# I-GAUGE_arduino_pro_mini_Instalasi_2.net
KiCad netlist of a schematic drawn in EAGLE
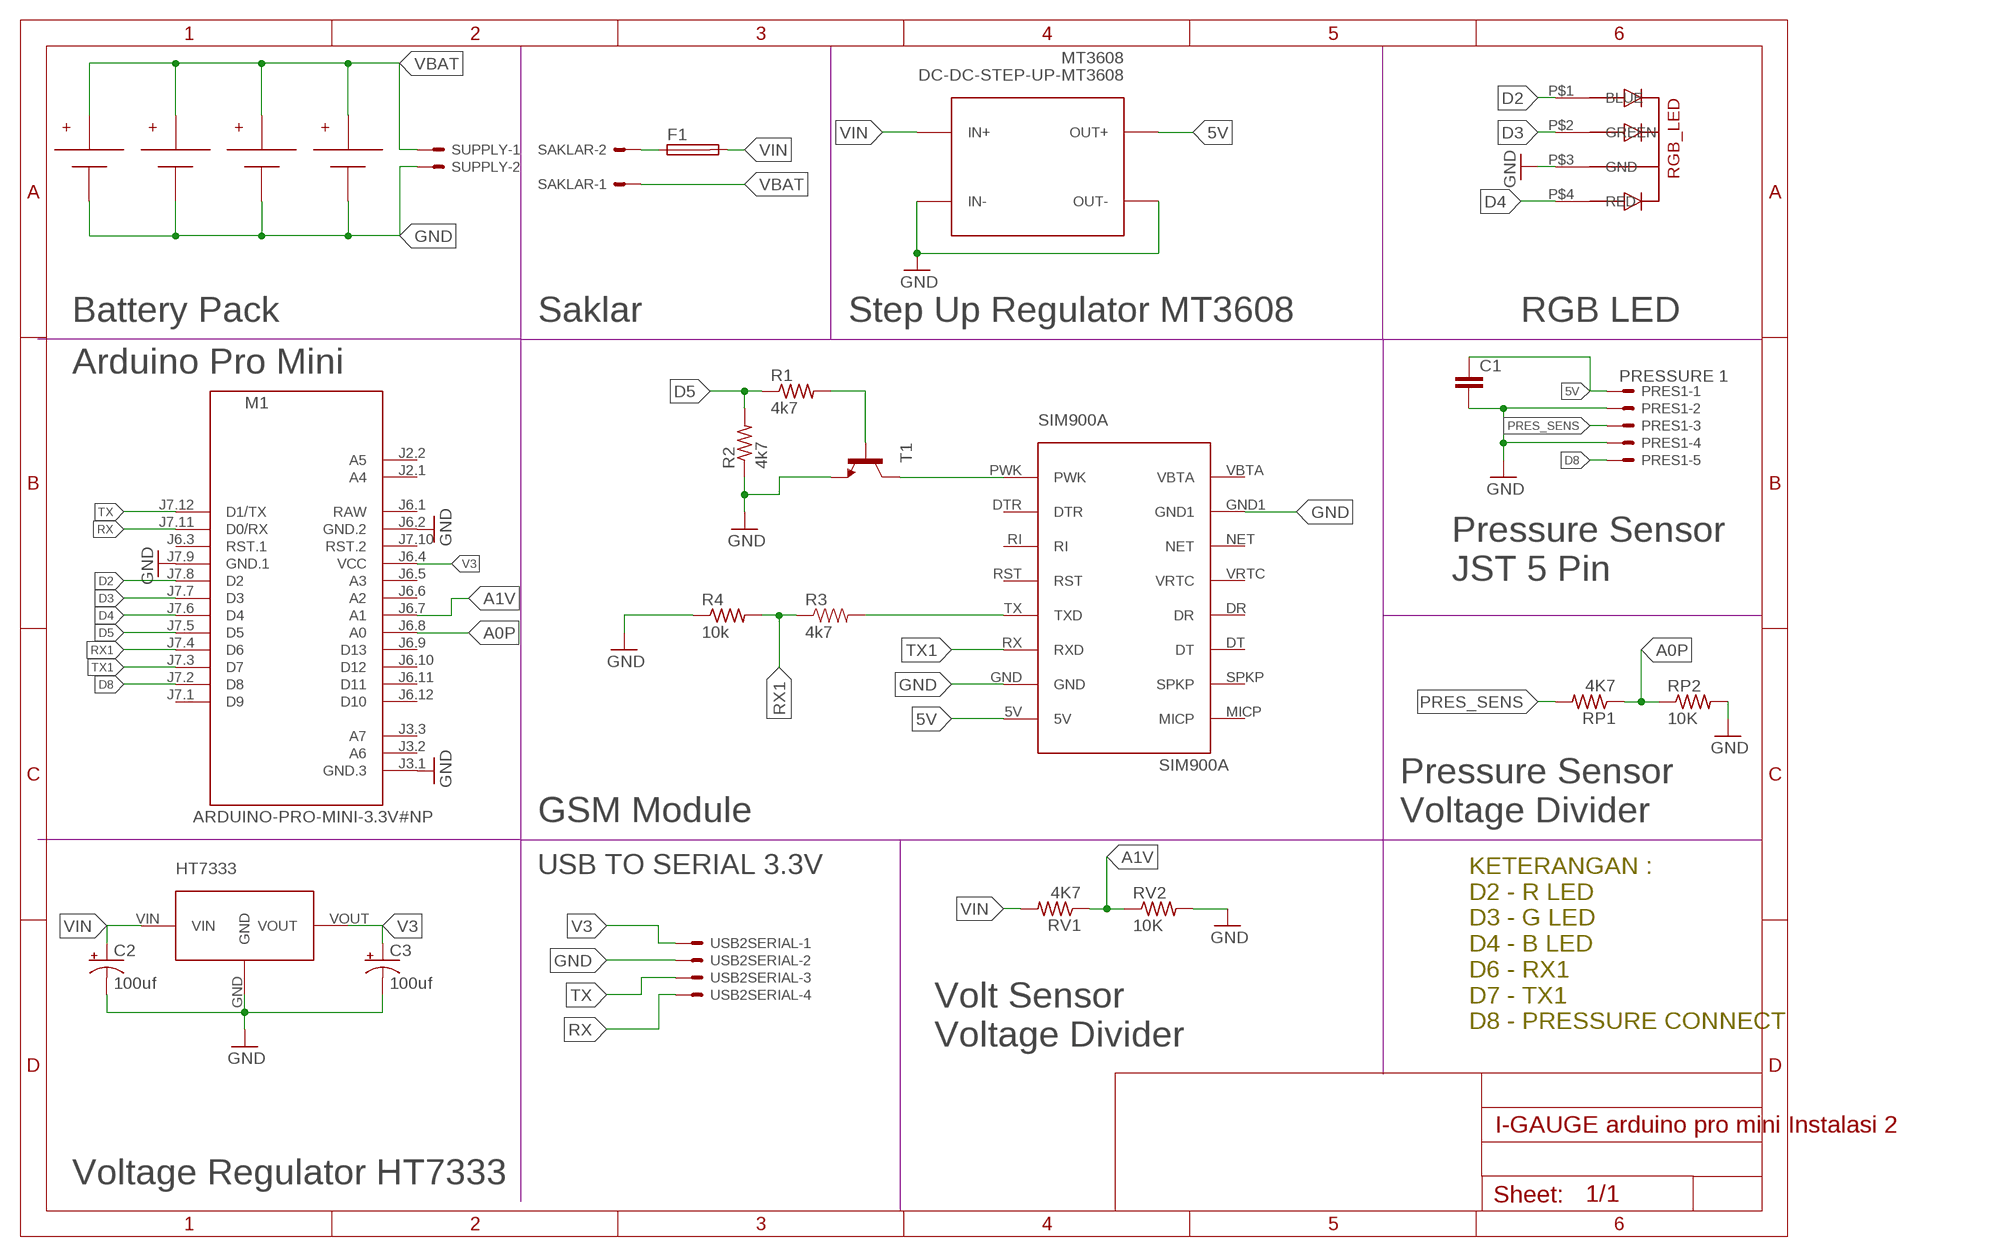
[diagram p0: schematic, sheet 1]

(export (version "E")
  (design (tool "Eeschema 10.0.6"))
  (components
    (comp (ref "C1")
      (value "C-EUC1206")
      (footprint "eagle-import:C1206")
      (libsource (lib "eagle-import") (part "C-EUC1206"))
    )
    (comp (ref "C2")
      (value "100uf")
      (footprint "eagle-import:CT7343")
      (libsource (lib "eagle-import") (part "CPOL-USCT7343"))
    )
    (comp (ref "C3")
      (value "100uf")
      (footprint "eagle-import:CT7343")
      (libsource (lib "eagle-import") (part "CPOL-USCT7343"))
    )
    (comp (ref "F1")
      (value "FUSESH22,5")
      (footprint "eagle-import:SH22,5")
      (libsource (lib "eagle-import") (part "FUSESH22,5"))
    )
    (comp (ref "HT7333")
      (value "HT7333_SOT89")
      (footprint "eagle-import:SOT89")
      (libsource (lib "eagle-import") (part "HT7333_SOT89"))
    )
    (comp (ref "M1")
      (value "ARDUINO-PRO-MINI-3.3V#NP")
      (footprint "eagle-import:ARDUINO-PRO-MINI#NP")
      (libsource (lib "eagle-import") (part "ARDUINO-PRO-MINI-#NP3.3V"))
    )
    (comp (ref "MT3608")
      (value "DC-DC-STEP-UP-MT3608")
      (footprint "eagle-import:DC-DC-STEP-UP-MT3608")
      (libsource (lib "eagle-import") (part "DC-DC-STEP-UP-MT3608"))
    )
    (comp (ref "PRES1")
      (value "PRESSURE 1")
      (footprint "eagle-import:JST-XH-05-PACKAGE-ROUND-PAD")
      (libsource (lib "eagle-import") (part "JST-XH-05-PIN-ROUND-PAD"))
    )
    (comp (ref "R1")
      (value "4k7")
      (footprint "eagle-import:R1206")
      (libsource (lib "eagle-import") (part "R-US_R1206"))
    )
    (comp (ref "R2")
      (value "4k7")
      (footprint "eagle-import:R1206")
      (libsource (lib "eagle-import") (part "R-US_R1206"))
    )
    (comp (ref "R3")
      (value "4k7")
      (footprint "eagle-import:1206")
      (libsource (lib "eagle-import") (part "RESISTOR1206"))
    )
    (comp (ref "R4")
      (value "10k")
      (footprint "eagle-import:R1206")
      (libsource (lib "eagle-import") (part "R-US_R1206"))
    )
    (comp (ref "RGB_LED")
      (value "5MMRGBLED")
      (footprint "eagle-import:LED5MMRGB")
      (libsource (lib "eagle-import") (part "5MMRGBLED"))
    )
    (comp (ref "RP1")
      (value "4K7")
      (footprint "eagle-import:M1206")
      (libsource (lib "eagle-import") (part "R-US_M1206"))
    )
    (comp (ref "RP2")
      (value "10K")
      (footprint "eagle-import:M1206")
      (libsource (lib "eagle-import") (part "R-US_M1206"))
    )
    (comp (ref "RV1")
      (value "4K7")
      (footprint "eagle-import:M1206")
      (libsource (lib "eagle-import") (part "R-US_M1206"))
    )
    (comp (ref "RV2")
      (value "10K")
      (footprint "eagle-import:M1206")
      (libsource (lib "eagle-import") (part "R-US_M1206"))
    )
    (comp (ref "SAKLAR")
      (value "JST-XH-02-PIN-ROUND-PAD")
      (footprint "eagle-import:JST-XH-02-PACKAGE-ROUND-PAD")
      (libsource (lib "eagle-import") (part "JST-XH-02-PIN-ROUND-PAD"))
    )
    (comp (ref "SUPPLY")
      (value "JST-XH-02-PIN-ROUND-PAD")
      (footprint "eagle-import:JST-XH-02-PACKAGE-ROUND-PAD")
      (libsource (lib "eagle-import") (part "JST-XH-02-PIN-ROUND-PAD"))
    )
    (comp (ref "T1")
      (value "-NPN-TO92")
      (footprint "eagle-import:TO92")
      (libsource (lib "eagle-import") (part "-NPN-TO92"))
    )
    (comp (ref "U$1")
      (value "SMT18650")
      (footprint "eagle-import:18650SMT")
      (libsource (lib "eagle-import") (part "SMT18650"))
    )
    (comp (ref "U$2")
      (value "SMT18650")
      (footprint "eagle-import:18650SMT")
      (libsource (lib "eagle-import") (part "SMT18650"))
    )
    (comp (ref "U$3")
      (value "SMT18650")
      (footprint "eagle-import:18650SMT")
      (libsource (lib "eagle-import") (part "SMT18650"))
    )
    (comp (ref "U$4")
      (value "SMT18650")
      (footprint "eagle-import:18650SMT")
      (libsource (lib "eagle-import") (part "SMT18650"))
    )
    (comp (ref "U$6")
      (value "SIM900A")
      (footprint "eagle-import:SIM900A")
      (libsource (lib "eagle-import") (part "SIM900A"))
    )
    (comp (ref "USB2SERIAL")
      (value "JST-XH-04-PIN-ROUND-PAD")
      (footprint "eagle-import:JST-XH-04-PACKAGE-ROUND-PAD")
      (libsource (lib "eagle-import") (part "JST-XH-04-PIN-ROUND-PAD"))
    )
  )
  (nets
    (net (code "1") (name "/RAW") (class "Default")
      (node (ref "M1") (pin "J6.1") (pinfunction "RAW_J6.1") (pintype "power_in"))
    )
    (net (code "2") (name "5V") (class "Default")
      (node (ref "C1") (pin "1") (pinfunction "1_1") (pintype "passive"))
      (node (ref "MT3608") (pin "OUT+") (pinfunction "OUT+_OUT+") (pintype "bidirectional"))
      (node (ref "PRES1") (pin "1") (pinfunction "S_1") (pintype "passive"))
      (node (ref "U$6") (pin "5V") (pinfunction "5V_5V") (pintype "bidirectional"))
    )
    (net (code "3") (name "A0P") (class "Default")
      (node (ref "M1") (pin "J6.8") (pinfunction "A0_J6.8") (pintype "bidirectional"))
      (node (ref "RP1") (pin "1") (pinfunction "1_1") (pintype "passive"))
      (node (ref "RP2") (pin "1") (pinfunction "1_1") (pintype "passive"))
    )
    (net (code "4") (name "A1V") (class "Default")
      (node (ref "M1") (pin "J6.7") (pinfunction "A1_J6.7") (pintype "bidirectional"))
      (node (ref "RV1") (pin "1") (pinfunction "1_1") (pintype "passive"))
      (node (ref "RV2") (pin "1") (pinfunction "1_1") (pintype "passive"))
    )
    (net (code "5") (name "D2") (class "Default")
      (node (ref "M1") (pin "J7.8") (pinfunction "D2_J7.8") (pintype "bidirectional"))
      (node (ref "RGB_LED") (pin "P$1") (pinfunction "BLUE_P$1") (pintype "bidirectional"))
    )
    (net (code "6") (name "D3") (class "Default")
      (node (ref "M1") (pin "J7.7") (pinfunction "D3_J7.7") (pintype "bidirectional"))
      (node (ref "RGB_LED") (pin "P$2") (pinfunction "GREEN_P$2") (pintype "bidirectional"))
    )
    (net (code "7") (name "D4") (class "Default")
      (node (ref "M1") (pin "J7.6") (pinfunction "D4_J7.6") (pintype "bidirectional"))
      (node (ref "RGB_LED") (pin "P$4") (pinfunction "RED_P$4") (pintype "bidirectional"))
    )
    (net (code "8") (name "D5") (class "Default")
      (node (ref "M1") (pin "J7.5") (pinfunction "D5_J7.5") (pintype "bidirectional"))
      (node (ref "R1") (pin "1") (pinfunction "1_1") (pintype "passive"))
      (node (ref "R2") (pin "2") (pinfunction "2_2") (pintype "passive"))
    )
    (net (code "9") (name "D8") (class "Default")
      (node (ref "M1") (pin "J7.2") (pinfunction "D8_J7.2") (pintype "bidirectional"))
      (node (ref "PRES1") (pin "5") (pinfunction "S_5") (pintype "passive"))
    )
    (net (code "10") (name "GND") (class "Default")
      (node (ref "C1") (pin "2") (pinfunction "2_2") (pintype "passive"))
      (node (ref "C2") (pin "-") (pinfunction "-_-") (pintype "passive"))
      (node (ref "C3") (pin "-") (pinfunction "-_-") (pintype "passive"))
      (node (ref "HT7333") (pin "GND") (pinfunction "GND_GND") (pintype "bidirectional"))
      (node (ref "M1") (pin "J3.1") (pinfunction "GND.3_J3.1") (pintype "bidirectional"))
      (node (ref "M1") (pin "J6.2") (pinfunction "GND.2_J6.2") (pintype "power_in"))
      (node (ref "M1") (pin "J7.9") (pinfunction "GND.1_J7.9") (pintype "power_in"))
      (node (ref "MT3608") (pin "IN-") (pinfunction "IN-_IN-") (pintype "bidirectional"))
      (node (ref "MT3608") (pin "OUT-") (pinfunction "OUT-_OUT-") (pintype "bidirectional"))
      (node (ref "PRES1") (pin "2") (pinfunction "S_2") (pintype "passive"))
      (node (ref "PRES1") (pin "4") (pinfunction "S_4") (pintype "passive"))
      (node (ref "R2") (pin "1") (pinfunction "1_1") (pintype "passive"))
      (node (ref "R4") (pin "1") (pinfunction "1_1") (pintype "passive"))
      (node (ref "RGB_LED") (pin "P$3") (pinfunction "GND_P$3") (pintype "bidirectional"))
      (node (ref "RP2") (pin "2") (pinfunction "2_2") (pintype "passive"))
      (node (ref "RV2") (pin "2") (pinfunction "2_2") (pintype "passive"))
      (node (ref "SUPPLY") (pin "2") (pinfunction "S_2") (pintype "passive"))
      (node (ref "T1") (pin "1") (pinfunction "E_1") (pintype "passive"))
      (node (ref "U$1") (pin "BATTERY_NEGATIVE") (pinfunction "-_BATTERY_NEGATIVE") (pintype "bidirectional"))
      (node (ref "U$2") (pin "BATTERY_NEGATIVE") (pinfunction "-_BATTERY_NEGATIVE") (pintype "bidirectional"))
      (node (ref "U$3") (pin "BATTERY_NEGATIVE") (pinfunction "-_BATTERY_NEGATIVE") (pintype "bidirectional"))
      (node (ref "U$4") (pin "BATTERY_NEGATIVE") (pinfunction "-_BATTERY_NEGATIVE") (pintype "bidirectional"))
      (node (ref "U$6") (pin "GND") (pinfunction "GND_GND") (pintype "bidirectional"))
      (node (ref "U$6") (pin "GND1") (pinfunction "GND1_GND1") (pintype "bidirectional"))
      (node (ref "USB2SERIAL") (pin "2") (pinfunction "S_2") (pintype "passive"))
    )
    (net (code "11") (name "Net-(SAKLARB-S)") (class "Default")
      (node (ref "F1") (pin "1") (pinfunction "1_1") (pintype "passive"))
      (node (ref "SAKLAR") (pin "2") (pinfunction "S_2") (pintype "passive"))
    )
    (net (code "12") (name "Net-(T1-B)") (class "Default")
      (node (ref "R1") (pin "2") (pinfunction "2_2") (pintype "passive"))
      (node (ref "T1") (pin "2") (pinfunction "B_2") (pintype "passive"))
    )
    (net (code "13") (name "Net-(T1-C)") (class "Default")
      (node (ref "T1") (pin "3") (pinfunction "C_3") (pintype "passive"))
      (node (ref "U$6") (pin "PWK") (pinfunction "PWK_PWK") (pintype "bidirectional"))
    )
    (net (code "14") (name "Net-(U$6-TXD)") (class "Default")
      (node (ref "R3") (pin "2") (pinfunction "2_2") (pintype "passive"))
      (node (ref "U$6") (pin "TX") (pinfunction "TXD_TX") (pintype "bidirectional"))
    )
    (net (code "15") (name "PRES_SENS") (class "Default")
      (node (ref "PRES1") (pin "3") (pinfunction "S_3") (pintype "passive"))
      (node (ref "RP1") (pin "2") (pinfunction "2_2") (pintype "passive"))
    )
    (net (code "16") (name "RX") (class "Default")
      (node (ref "M1") (pin "J7.11") (pinfunction "D0/RX_J7.11") (pintype "bidirectional"))
      (node (ref "USB2SERIAL") (pin "4") (pinfunction "S_4") (pintype "passive"))
    )
    (net (code "17") (name "RX1") (class "Default")
      (node (ref "M1") (pin "J7.4") (pinfunction "D6_J7.4") (pintype "bidirectional"))
      (node (ref "R3") (pin "1") (pinfunction "1_1") (pintype "passive"))
      (node (ref "R4") (pin "2") (pinfunction "2_2") (pintype "passive"))
    )
    (net (code "18") (name "TX") (class "Default")
      (node (ref "M1") (pin "J7.12") (pinfunction "D1/TX_J7.12") (pintype "bidirectional"))
      (node (ref "USB2SERIAL") (pin "3") (pinfunction "S_3") (pintype "passive"))
    )
    (net (code "19") (name "TX1") (class "Default")
      (node (ref "M1") (pin "J7.3") (pinfunction "D7_J7.3") (pintype "bidirectional"))
      (node (ref "U$6") (pin "RX") (pinfunction "RXD_RX") (pintype "bidirectional"))
    )
    (net (code "20") (name "V3") (class "Default")
      (node (ref "C3") (pin "+") (pinfunction "+_+") (pintype "passive"))
      (node (ref "HT7333") (pin "VOUT") (pinfunction "VOUT_VOUT") (pintype "bidirectional"))
      (node (ref "M1") (pin "J6.4") (pinfunction "VCC_J6.4") (pintype "power_in"))
      (node (ref "USB2SERIAL") (pin "1") (pinfunction "S_1") (pintype "passive"))
    )
    (net (code "21") (name "VBAT") (class "Default")
      (node (ref "SAKLAR") (pin "1") (pinfunction "S_1") (pintype "passive"))
      (node (ref "SUPPLY") (pin "1") (pinfunction "S_1") (pintype "passive"))
      (node (ref "U$1") (pin "BATTERY_POSITIVE") (pinfunction "+_BATTERY_POSITIVE") (pintype "bidirectional"))
      (node (ref "U$2") (pin "BATTERY_POSITIVE") (pinfunction "+_BATTERY_POSITIVE") (pintype "bidirectional"))
      (node (ref "U$3") (pin "BATTERY_POSITIVE") (pinfunction "+_BATTERY_POSITIVE") (pintype "bidirectional"))
      (node (ref "U$4") (pin "BATTERY_POSITIVE") (pinfunction "+_BATTERY_POSITIVE") (pintype "bidirectional"))
    )
    (net (code "22") (name "VIN") (class "Default")
      (node (ref "C2") (pin "+") (pinfunction "+_+") (pintype "passive"))
      (node (ref "F1") (pin "2") (pinfunction "2_2") (pintype "passive"))
      (node (ref "HT7333") (pin "VIN") (pinfunction "VIN_VIN") (pintype "bidirectional"))
      (node (ref "MT3608") (pin "IN+") (pinfunction "IN+_IN+") (pintype "bidirectional"))
      (node (ref "RV1") (pin "2") (pinfunction "2_2") (pintype "passive"))
    )
    (net (code "23") (name "unconnected-(M1-A2-PadJ6.6)") (class "Default")
      (node (ref "M1") (pin "J6.6") (pinfunction "A2_J6.6") (pintype "bidirectional"))
    )
    (net (code "24") (name "unconnected-(M1-A3-PadJ6.5)") (class "Default")
      (node (ref "M1") (pin "J6.5") (pinfunction "A3_J6.5") (pintype "bidirectional"))
    )
    (net (code "25") (name "unconnected-(M1-A4-PadJ2.1)") (class "Default")
      (node (ref "M1") (pin "J2.1") (pinfunction "A4_J2.1") (pintype "bidirectional"))
    )
    (net (code "26") (name "unconnected-(M1-A5-PadJ2.2)") (class "Default")
      (node (ref "M1") (pin "J2.2") (pinfunction "A5_J2.2") (pintype "bidirectional"))
    )
    (net (code "27") (name "unconnected-(M1-A6-PadJ3.2)") (class "Default")
      (node (ref "M1") (pin "J3.2") (pinfunction "A6_J3.2") (pintype "bidirectional"))
    )
    (net (code "28") (name "unconnected-(M1-A7-PadJ3.3)") (class "Default")
      (node (ref "M1") (pin "J3.3") (pinfunction "A7_J3.3") (pintype "bidirectional"))
    )
    (net (code "29") (name "unconnected-(M1-D9-PadJ7.1)") (class "Default")
      (node (ref "M1") (pin "J7.1") (pinfunction "D9_J7.1") (pintype "bidirectional"))
    )
    (net (code "30") (name "unconnected-(M1-D10-PadJ6.12)") (class "Default")
      (node (ref "M1") (pin "J6.12") (pinfunction "D10_J6.12") (pintype "bidirectional"))
    )
    (net (code "31") (name "unconnected-(M1-D11-PadJ6.11)") (class "Default")
      (node (ref "M1") (pin "J6.11") (pinfunction "D11_J6.11") (pintype "bidirectional"))
    )
    (net (code "32") (name "unconnected-(M1-D12-PadJ6.10)") (class "Default")
      (node (ref "M1") (pin "J6.10") (pinfunction "D12_J6.10") (pintype "bidirectional"))
    )
    (net (code "33") (name "unconnected-(M1-D13-PadJ6.9)") (class "Default")
      (node (ref "M1") (pin "J6.9") (pinfunction "D13_J6.9") (pintype "bidirectional"))
    )
    (net (code "34") (name "unconnected-(M1-RST.1-PadJ6.3)") (class "Default")
      (node (ref "M1") (pin "J6.3") (pinfunction "RST.1_J6.3") (pintype "bidirectional"))
    )
    (net (code "35") (name "unconnected-(M1-RST.2-PadJ7.10)") (class "Default")
      (node (ref "M1") (pin "J7.10") (pinfunction "RST.2_J7.10") (pintype "bidirectional"))
    )
    (net (code "36") (name "unconnected-(U$6-PadDR)") (class "Default")
      (node (ref "U$6") (pin "DR") (pinfunction "DR_DR") (pintype "bidirectional"))
    )
    (net (code "37") (name "unconnected-(U$6-PadDT)") (class "Default")
      (node (ref "U$6") (pin "DT") (pinfunction "DT_DT") (pintype "bidirectional"))
    )
    (net (code "38") (name "unconnected-(U$6-PadDTR)") (class "Default")
      (node (ref "U$6") (pin "DTR") (pinfunction "DTR_DTR") (pintype "bidirectional"))
    )
    (net (code "39") (name "unconnected-(U$6-PadMICP)") (class "Default")
      (node (ref "U$6") (pin "MICP") (pinfunction "MICP_MICP") (pintype "bidirectional"))
    )
    (net (code "40") (name "unconnected-(U$6-PadNET)") (class "Default")
      (node (ref "U$6") (pin "NET") (pinfunction "NET_NET") (pintype "bidirectional"))
    )
    (net (code "41") (name "unconnected-(U$6-PadRI)") (class "Default")
      (node (ref "U$6") (pin "RI") (pinfunction "RI_RI") (pintype "bidirectional"))
    )
    (net (code "42") (name "unconnected-(U$6-PadRST)") (class "Default")
      (node (ref "U$6") (pin "RST") (pinfunction "RST_RST") (pintype "bidirectional"))
    )
    (net (code "43") (name "unconnected-(U$6-PadSPKP)") (class "Default")
      (node (ref "U$6") (pin "SPKP") (pinfunction "SPKP_SPKP") (pintype "bidirectional"))
    )
    (net (code "44") (name "unconnected-(U$6-PadVBTA)") (class "Default")
      (node (ref "U$6") (pin "VBTA") (pinfunction "VBTA_VBTA") (pintype "bidirectional"))
    )
    (net (code "45") (name "unconnected-(U$6-PadVRTC)") (class "Default")
      (node (ref "U$6") (pin "VRTC") (pinfunction "VRTC_VRTC") (pintype "bidirectional"))
    )
  )
)
